# Battery_Level_Indicator.net
KiCad netlist of a schematic drawn in Altium Designer
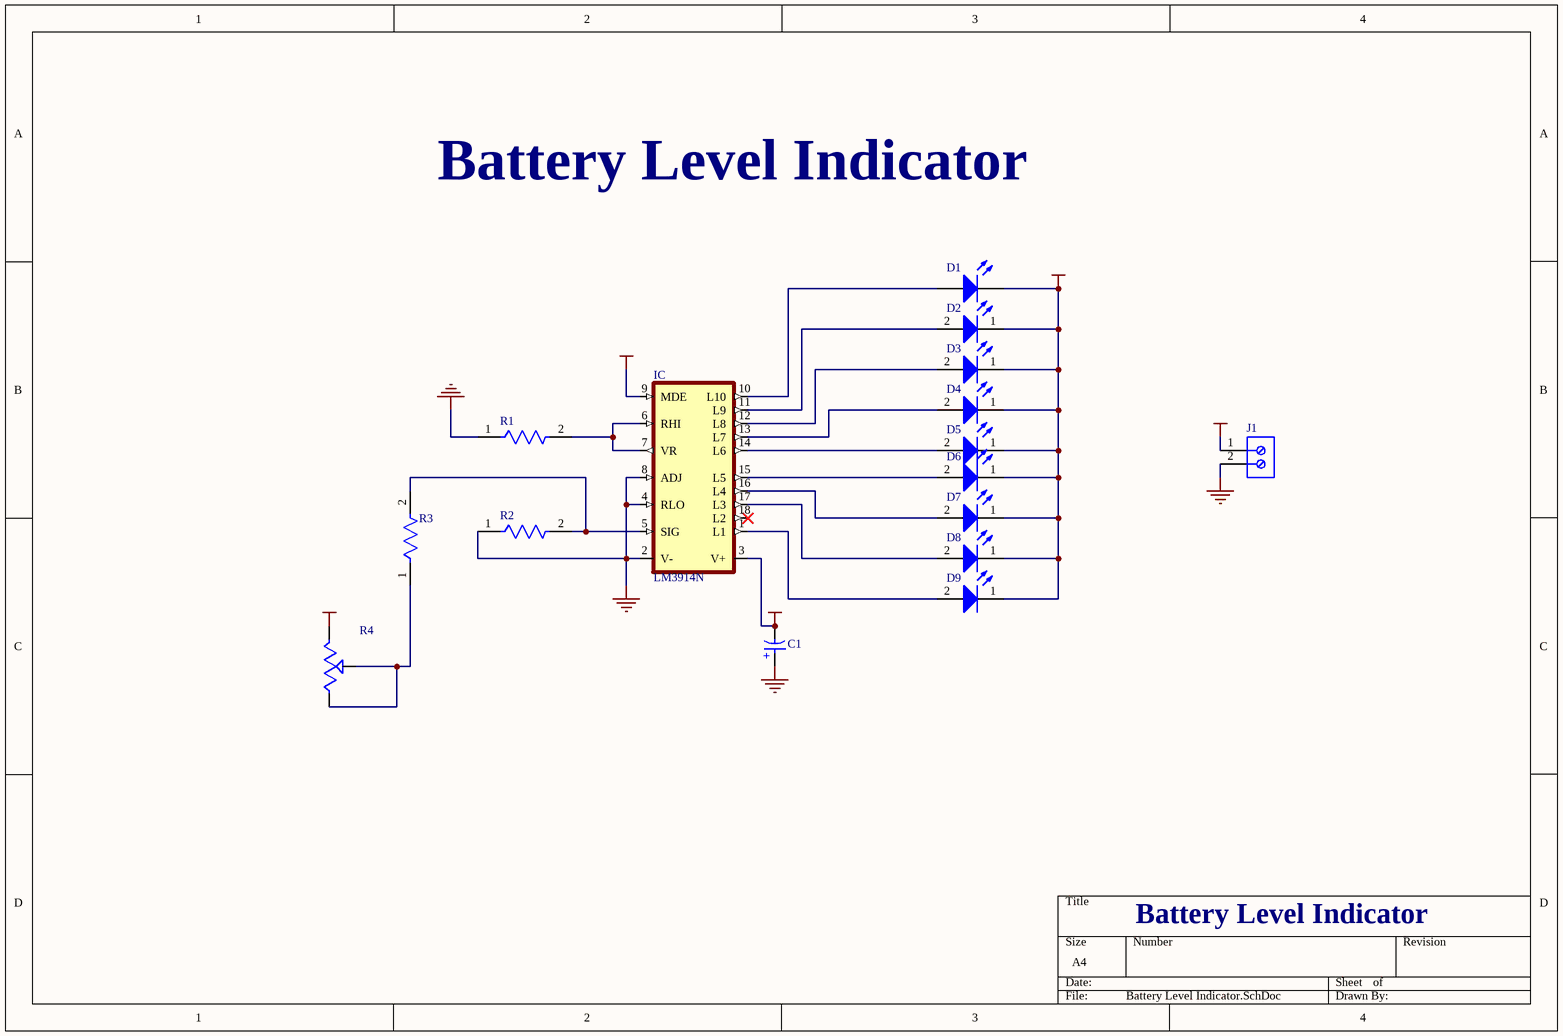
[diagram p0: Battery Level Indicator.SchDoc]

(export (version "E")
  (design (tool "Eeschema 10.0.6"))
  (components
    (comp (ref "C1")
      (value "860130272001")
      (footprint "WCAP-ATET_D5H11")
      (description "860130272001 WCAP-ATET Aluminum Electrolytic Capacitors")
      (fields (field (name "TOLERANCE") "20%"))
      (libsource (lib "Altium Content Vault") (part "Capacitor_Polarized"))
    )
    (comp (ref "D1")
      (value "15400385A3590")
      (footprint "WL-TIRW_D3.9H5.3")
      (description "15400385A3590 WL-TIRW THT Infrared Round Waterclear")
      (libsource (lib "") (part "LED_Infrared_2A-1K_1"))
    )
    (comp (ref "D2")
      (value "15400385A3590")
      (footprint "WL-TIRW_D3.9H5.3")
      (description "15400385A3590 WL-TIRW THT Infrared Round Waterclear")
      (libsource (lib "Altium Content Vault") (part "LED_Infrared_2A-1K"))
    )
    (comp (ref "D3")
      (value "15400385A3590")
      (footprint "WL-TIRW_D3.9H5.3")
      (description "15400385A3590 WL-TIRW THT Infrared Round Waterclear")
      (libsource (lib "Altium Content Vault") (part "LED_Infrared_2A-1K"))
    )
    (comp (ref "D4")
      (value "15400385A3590")
      (footprint "WL-TIRW_D3.9H5.3")
      (description "15400385A3590 WL-TIRW THT Infrared Round Waterclear")
      (libsource (lib "Altium Content Vault") (part "LED_Infrared_2A-1K"))
    )
    (comp (ref "D5")
      (value "15400385A3590")
      (footprint "WL-TIRW_D3.9H5.3")
      (description "15400385A3590 WL-TIRW THT Infrared Round Waterclear")
      (libsource (lib "Altium Content Vault") (part "LED_Infrared_2A-1K"))
    )
    (comp (ref "D6")
      (value "15400385A3590")
      (footprint "WL-TIRW_D3.9H5.3")
      (description "15400385A3590 WL-TIRW THT Infrared Round Waterclear")
      (libsource (lib "Altium Content Vault") (part "LED_Infrared_2A-1K"))
    )
    (comp (ref "D7")
      (value "15400385A3590")
      (footprint "WL-TIRW_D3.9H5.3")
      (description "15400385A3590 WL-TIRW THT Infrared Round Waterclear")
      (libsource (lib "Altium Content Vault") (part "LED_Infrared_2A-1K"))
    )
    (comp (ref "D8")
      (value "15400385A3590")
      (footprint "WL-TIRW_D3.9H5.3")
      (description "15400385A3590 WL-TIRW THT Infrared Round Waterclear")
      (libsource (lib "Altium Content Vault") (part "LED_Infrared_2A-1K"))
    )
    (comp (ref "D9")
      (value "15400385A3590")
      (footprint "WL-TIRW_D3.9H5.3")
      (description "15400385A3590 WL-TIRW THT Infrared Round Waterclear")
      (libsource (lib "Altium Content Vault") (part "LED_Infrared_2A-1K"))
    )
    (comp (ref "IC")
      (value "LM3914N")
      (footprint "DIL18")
      (description "LED Lighting Drivers")
      (fields (field (name "MF") "Texas Instruments"))
      (libsource (lib "LM3914N") (part "LM3914N"))
    )
    (comp (ref "J1")
      (value "691101710002")
      (footprint "691101710002")
      (fields (field (name "VOLTAGE") "250V"))
      (libsource (lib "Altium Content Vault") (part "TBL - 1R - 02P - Screw"))
    )
    (comp (ref "R1")
      (value "MRS25000C1000FRP00")
      (footprint "FP-MRS25-MFG")
      (fields (field (name "TOLERANCE") "1%"))
      (libsource (lib "Altium Content Vault") (part "1029c3af85768c4190bb7ad29bc67b5"))
    )
    (comp (ref "R2")
      (value "MRS25000C1000FRP00")
      (footprint "FP-MRS25-MFG")
      (fields (field (name "TOLERANCE") "1%"))
      (libsource (lib "Altium Content Vault") (part "1029c3af85768c4190bb7ad29bc67b5"))
    )
    (comp (ref "R3")
      (value "MRS25000C1000FRP00")
      (footprint "FP-MRS25-MFG")
      (fields (field (name "TOLERANCE") "1%"))
      (libsource (lib "Altium Content Vault") (part "1029c3af85768c4190bb7ad29bc67b5"))
    )
    (comp (ref "R4")
      (value "EVN-D8AA03B14")
      (footprint "TRIM_EVN-D8AA03B14")
      (description "10 kOhms 0.1W, 1/10W PC Pins Through Hole Trimmer Potentiometer Carbon 1.0 Turn Top Adjustment")
      (fields (field (name "MF") "Panasonic Electronic"))
      (libsource (lib "EVN-D8AA03B14") (part "EVN-D8AA03B14"))
    )
  )
  (nets
    (net (code "1") (name "GND") (class "Default")
      (node (ref "C1") (pin "1") (pinfunction "P_1") (pintype "passive"))
      (node (ref "IC") (pin "2") (pinfunction "V-_2") (pintype "power_in"))
      (node (ref "IC") (pin "4") (pinfunction "RLO_4") (pintype "input"))
      (node (ref "IC") (pin "8") (pinfunction "ADJ_8") (pintype "input"))
      (node (ref "J1") (pin "2") (pinfunction "2_2") (pintype "passive"))
      (node (ref "R1") (pin "1") (pinfunction "1_1") (pintype "passive"))
      (node (ref "R2") (pin "1") (pinfunction "1_1") (pintype "passive"))
    )
    (net (code "2") (name "Net-(D1-A)") (class "Default")
      (node (ref "D1") (pin "2") (pinfunction "A_2") (pintype "passive"))
      (node (ref "IC") (pin "10") (pinfunction "L10_10") (pintype "output"))
    )
    (net (code "3") (name "Net-(D2-A)") (class "Default")
      (node (ref "D2") (pin "2") (pinfunction "A_2") (pintype "passive"))
      (node (ref "IC") (pin "11") (pinfunction "L9_11") (pintype "output"))
    )
    (net (code "4") (name "Net-(D3-A)") (class "Default")
      (node (ref "D3") (pin "2") (pinfunction "A_2") (pintype "passive"))
      (node (ref "IC") (pin "12") (pinfunction "L8_12") (pintype "output"))
    )
    (net (code "5") (name "Net-(D4-A)") (class "Default")
      (node (ref "D4") (pin "2") (pinfunction "A_2") (pintype "passive"))
      (node (ref "IC") (pin "13") (pinfunction "L7_13") (pintype "output"))
    )
    (net (code "6") (name "Net-(D5-A)") (class "Default")
      (node (ref "D5") (pin "2") (pinfunction "A_2") (pintype "passive"))
      (node (ref "IC") (pin "14") (pinfunction "L6_14") (pintype "output"))
    )
    (net (code "7") (name "Net-(D6-A)") (class "Default")
      (node (ref "D6") (pin "2") (pinfunction "A_2") (pintype "passive"))
      (node (ref "IC") (pin "15") (pinfunction "L5_15") (pintype "output"))
    )
    (net (code "8") (name "Net-(D7-A)") (class "Default")
      (node (ref "D7") (pin "2") (pinfunction "A_2") (pintype "passive"))
      (node (ref "IC") (pin "16") (pinfunction "L4_16") (pintype "output"))
    )
    (net (code "9") (name "Net-(D8-A)") (class "Default")
      (node (ref "D8") (pin "2") (pinfunction "A_2") (pintype "passive"))
      (node (ref "IC") (pin "17") (pinfunction "L3_17") (pintype "output"))
    )
    (net (code "10") (name "Net-(D9-A)") (class "Default")
      (node (ref "D9") (pin "2") (pinfunction "A_2") (pintype "passive"))
      (node (ref "IC") (pin "1") (pinfunction "L1_1") (pintype "output"))
    )
    (net (code "11") (name "Net-(IC-RHI)") (class "Default")
      (node (ref "IC") (pin "6") (pinfunction "RHI_6") (pintype "input"))
      (node (ref "IC") (pin "7") (pinfunction "VR_7") (pintype "output"))
      (node (ref "R1") (pin "2") (pinfunction "2_2") (pintype "passive"))
    )
    (net (code "12") (name "Net-(IC-SIG)") (class "Default")
      (node (ref "IC") (pin "5") (pinfunction "SIG_5") (pintype "input"))
      (node (ref "R2") (pin "2") (pinfunction "2_2") (pintype "passive"))
      (node (ref "R3") (pin "2") (pinfunction "2_2") (pintype "passive"))
    )
    (net (code "13") (name "Net-(R3-Pad1)") (class "Default")
      (node (ref "R3") (pin "1") (pinfunction "1_1") (pintype "passive"))
      (node (ref "R4") (pin "1") (pinfunction "1_1") (pintype "passive"))
      (node (ref "R4") (pin "2") (pinfunction "2_2") (pintype "passive"))
    )
    (net (code "14") (name "VCC") (class "Default")
      (node (ref "C1") (pin "2") (pinfunction "N_2") (pintype "passive"))
      (node (ref "D1") (pin "1") (pinfunction "K_1") (pintype "passive"))
      (node (ref "D2") (pin "1") (pinfunction "K_1") (pintype "passive"))
      (node (ref "D3") (pin "1") (pinfunction "K_1") (pintype "passive"))
      (node (ref "D4") (pin "1") (pinfunction "K_1") (pintype "passive"))
      (node (ref "D5") (pin "1") (pinfunction "K_1") (pintype "passive"))
      (node (ref "D6") (pin "1") (pinfunction "K_1") (pintype "passive"))
      (node (ref "D7") (pin "1") (pinfunction "K_1") (pintype "passive"))
      (node (ref "D8") (pin "1") (pinfunction "K_1") (pintype "passive"))
      (node (ref "D9") (pin "1") (pinfunction "K_1") (pintype "passive"))
      (node (ref "IC") (pin "3") (pinfunction "V+_3") (pintype "power_in"))
      (node (ref "IC") (pin "9") (pinfunction "MDE_9") (pintype "input"))
      (node (ref "J1") (pin "1") (pinfunction "1_1") (pintype "passive"))
      (node (ref "R4") (pin "3") (pinfunction "3_3") (pintype "passive"))
    )
    (net (code "15") (name "unconnected-(IC-L2-Pad18)") (class "Default")
      (node (ref "IC") (pin "18") (pinfunction "L2_18") (pintype "output+no_connect"))
    )
  )
)
